# Raspi-TPUART.net
KiCad netlist of a schematic drawn in EAGLE
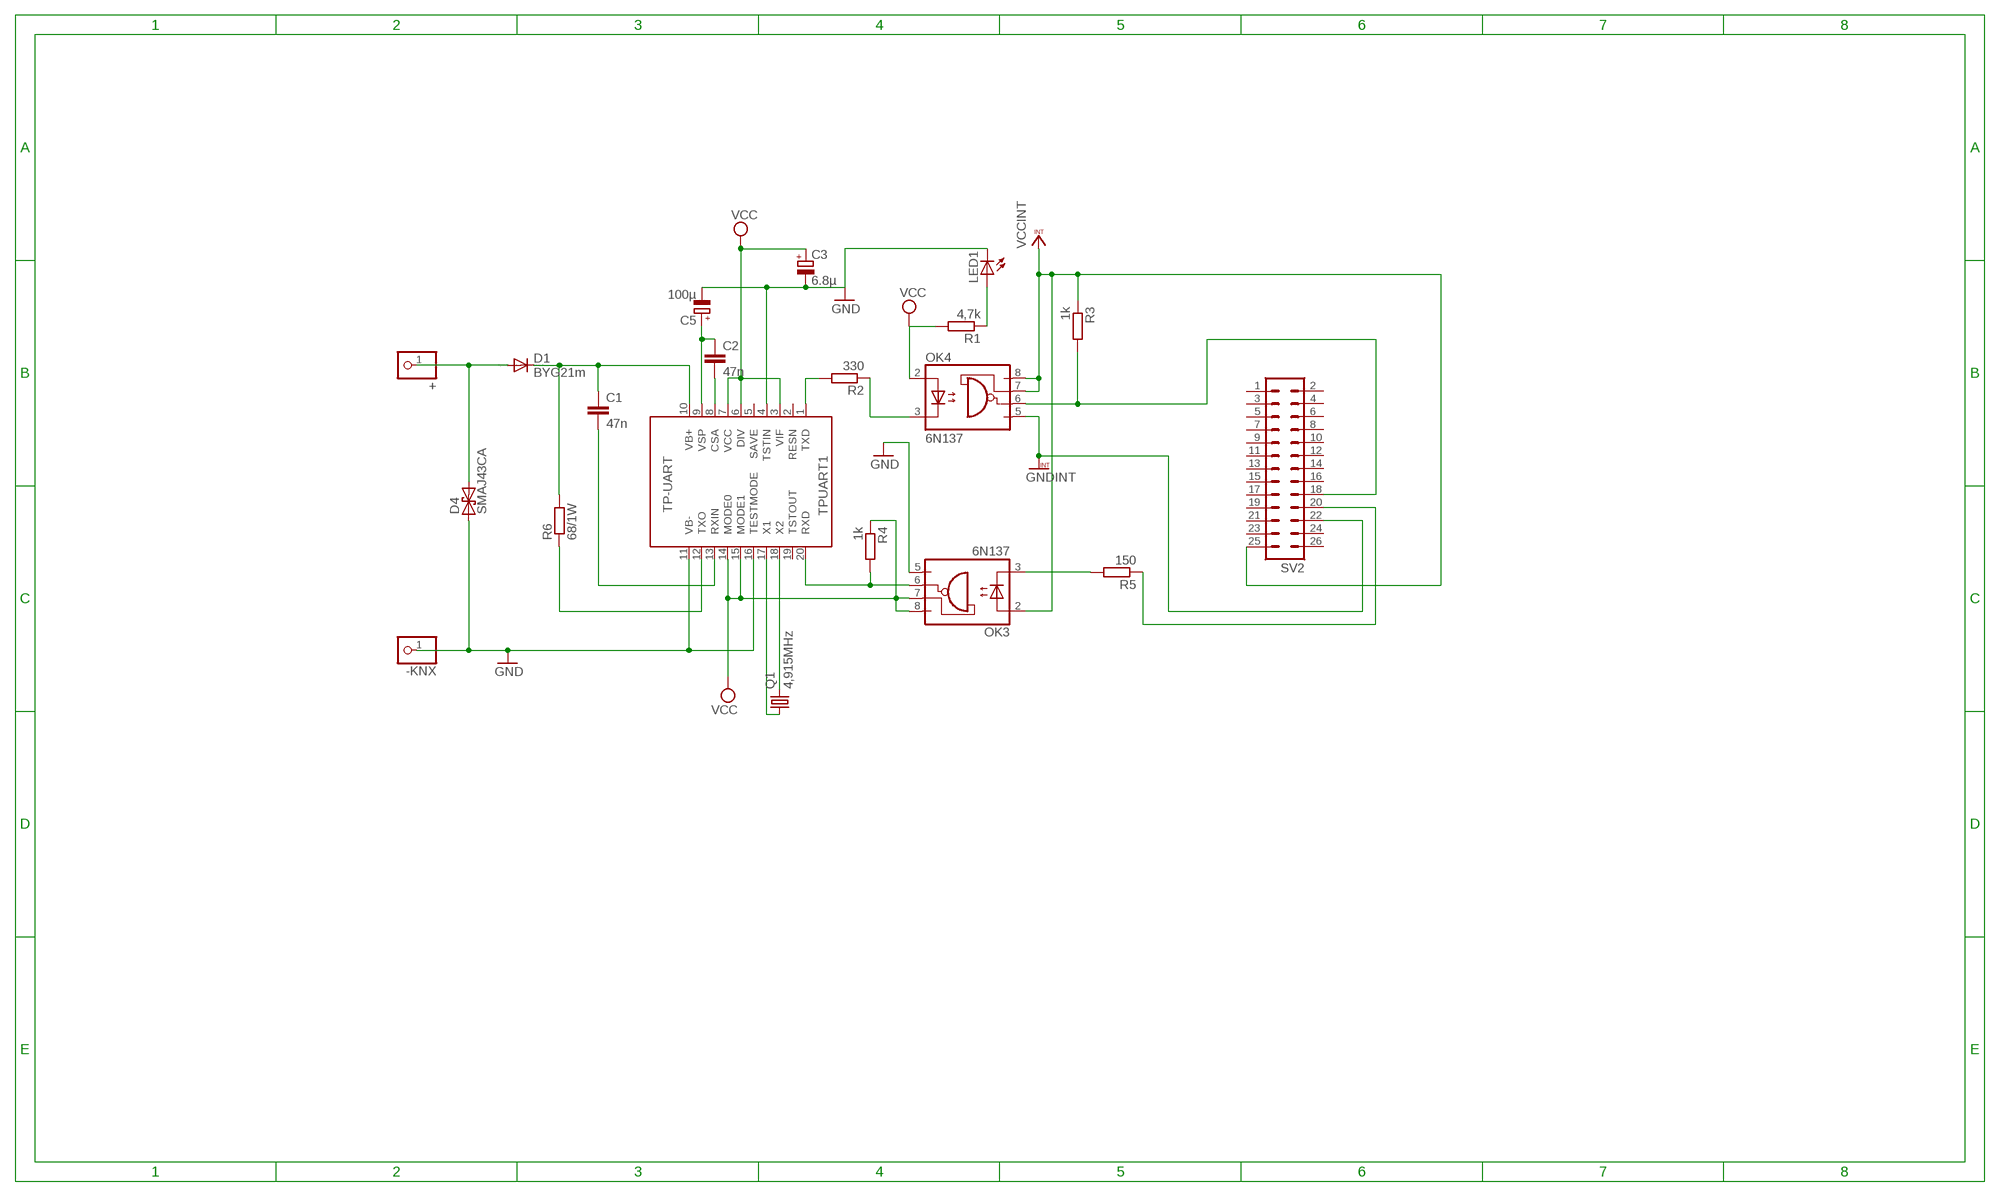
[diagram p0: schematic, sheet 1]

(export (version "E")
  (design (tool "Eeschema 10.0.6"))
  (components
    (comp (ref "+")
      (value "PINHD-1X1")
      (footprint "eagle-import:1X01")
      (libsource (lib "eagle-import") (part "PINHD-1X1"))
    )
    (comp (ref "-KNX")
      (value "PINHD-1X1")
      (footprint "eagle-import:1X01")
      (libsource (lib "eagle-import") (part "PINHD-1X1"))
    )
    (comp (ref "C1")
      (value "47n")
      (footprint "eagle-import:C1206")
      (libsource (lib "eagle-import") (part "C-EUC1206"))
    )
    (comp (ref "C2")
      (value "47n")
      (footprint "eagle-import:C1206")
      (libsource (lib "eagle-import") (part "C-EUC1206"))
    )
    (comp (ref "C3")
      (value "6.8µ")
      (footprint "eagle-import:CT7343")
      (libsource (lib "eagle-import") (part "CPOL-EUCT7343"))
    )
    (comp (ref "C5")
      (value "100µ")
      (footprint "eagle-import:CT7343")
      (libsource (lib "eagle-import") (part "CPOL-EUCT7343"))
    )
    (comp (ref "D1")
      (value "BYG21m")
      (footprint "eagle-import:SMB")
      (libsource (lib "eagle-import") (part "ES2D"))
    )
    (comp (ref "D4")
      (value "SMAJ43CA")
      (footprint "eagle-import:DO214AA")
      (libsource (lib "eagle-import") (part "BZW04XXB"))
    )
    (comp (ref "LED1")
      (value "LEDKA-3528ASYC")
      (footprint "eagle-import:KA-3528ASYC")
      (libsource (lib "eagle-import") (part "LEDKA-3528ASYC"))
    )
    (comp (ref "OK3")
      (value "6N137")
      (footprint "eagle-import:DIL8-SMD")
      (libsource (lib "eagle-import") (part "6N137"))
    )
    (comp (ref "OK4")
      (value "6N137")
      (footprint "eagle-import:DIL8-SMD")
      (libsource (lib "eagle-import") (part "6N137"))
    )
    (comp (ref "Q1")
      (value "4,915MHz")
      (footprint "eagle-import:HC49UP")
      (libsource (lib "eagle-import") (part "CRYSTALHC49UP"))
    )
    (comp (ref "R1")
      (value "4,7k")
      (footprint "eagle-import:M1206")
      (libsource (lib "eagle-import") (part "R-EU_M1206"))
    )
    (comp (ref "R2")
      (value "330")
      (footprint "eagle-import:M1206")
      (libsource (lib "eagle-import") (part "R-EU_M1206"))
    )
    (comp (ref "R3")
      (value "1k")
      (footprint "eagle-import:M1206")
      (libsource (lib "eagle-import") (part "R-EU_M1206"))
    )
    (comp (ref "R4")
      (value "1k")
      (footprint "eagle-import:M1206")
      (libsource (lib "eagle-import") (part "R-EU_M1206"))
    )
    (comp (ref "R5")
      (value "150")
      (footprint "eagle-import:M1206")
      (libsource (lib "eagle-import") (part "R-EU_M1206"))
    )
    (comp (ref "R6")
      (value "68/1W")
      (footprint "eagle-import:R2512")
      (libsource (lib "eagle-import") (part "R-EU_R2512"))
    )
    (comp (ref "SV2")
      (value "MA13-2")
      (footprint "eagle-import:MA13-2")
      (libsource (lib "eagle-import") (part "MA13-2"))
    )
    (comp (ref "TPUART1")
      (value "TP-UART")
      (footprint "eagle-import:SOIC20")
      (libsource (lib "eagle-import") (part "TP-UART"))
    )
  )
  (nets
    (net (code "1") (name "GND") (class "Default")
      (node (ref "-KNX") (pin "1") (pinfunction "1_1") (pintype "passive"))
      (node (ref "C3") (pin "-") (pinfunction "-_-") (pintype "passive"))
      (node (ref "C5") (pin "-") (pinfunction "-_-") (pintype "passive"))
      (node (ref "D4") (pin "A") (pinfunction "1_A") (pintype "passive"))
      (node (ref "LED1") (pin "C") (pinfunction "C_C") (pintype "passive"))
      (node (ref "OK3") (pin "5") (pinfunction "GND_5") (pintype "passive"))
      (node (ref "TPUART1") (pin "11") (pinfunction "VB-_11") (pintype "passive"))
      (node (ref "TPUART1") (pin "16") (pinfunction "TESTMODE_16") (pintype "input"))
      (node (ref "TPUART1") (pin "4") (pinfunction "TSTIN_4") (pintype "bidirectional"))
    )
    (net (code "2") (name "GNDINT") (class "Default")
      (node (ref "OK4") (pin "5") (pinfunction "GND_5") (pintype "passive"))
      (node (ref "SV2") (pin "22") (pinfunction "22_22") (pintype "passive"))
    )
    (net (code "3") (name "Net-(D4-2)") (class "Default")
      (node (ref "+") (pin "1") (pinfunction "1_1") (pintype "passive"))
      (node (ref "D1") (pin "A") (pinfunction "A_A") (pintype "passive"))
      (node (ref "D4") (pin "C") (pinfunction "2_C") (pintype "passive"))
    )
    (net (code "4") (name "Net-(LED1-PadA)") (class "Default")
      (node (ref "LED1") (pin "A") (pinfunction "A_A") (pintype "passive"))
      (node (ref "R1") (pin "1") (pinfunction "1_1") (pintype "passive"))
    )
    (net (code "5") (name "Net-(OK3-C)") (class "Default")
      (node (ref "OK3") (pin "3") (pinfunction "C_3") (pintype "passive"))
      (node (ref "R5") (pin "2") (pinfunction "2_2") (pintype "passive"))
    )
    (net (code "6") (name "Net-(OK3-VO)") (class "Default")
      (node (ref "OK3") (pin "6") (pinfunction "VO_6") (pintype "passive"))
      (node (ref "R4") (pin "2") (pinfunction "2_2") (pintype "passive"))
      (node (ref "TPUART1") (pin "20") (pinfunction "RXD_20") (pintype "input"))
    )
    (net (code "7") (name "Net-(OK4-C)") (class "Default")
      (node (ref "OK4") (pin "3") (pinfunction "C_3") (pintype "passive"))
      (node (ref "R2") (pin "1") (pinfunction "1_1") (pintype "passive"))
    )
    (net (code "8") (name "Net-(OK4-VO)") (class "Default")
      (node (ref "OK4") (pin "6") (pinfunction "VO_6") (pintype "passive"))
      (node (ref "R3") (pin "2") (pinfunction "2_2") (pintype "passive"))
      (node (ref "SV2") (pin "18") (pinfunction "18_18") (pintype "passive"))
    )
    (net (code "9") (name "Net-(R5-Pad1)") (class "Default")
      (node (ref "R5") (pin "1") (pinfunction "1_1") (pintype "passive"))
      (node (ref "SV2") (pin "20") (pinfunction "20_20") (pintype "passive"))
    )
    (net (code "10") (name "Net-(TPUART1-CSA)") (class "Default")
      (node (ref "C2") (pin "2") (pinfunction "2_2") (pintype "passive"))
      (node (ref "TPUART1") (pin "8") (pinfunction "CSA_8") (pintype "passive"))
    )
    (net (code "11") (name "Net-(TPUART1-RXIN)") (class "Default")
      (node (ref "C1") (pin "2") (pinfunction "2_2") (pintype "passive"))
      (node (ref "TPUART1") (pin "13") (pinfunction "RXIN_13") (pintype "input"))
    )
    (net (code "12") (name "Net-(TPUART1-TXD)") (class "Default")
      (node (ref "R2") (pin "2") (pinfunction "2_2") (pintype "passive"))
      (node (ref "TPUART1") (pin "1") (pinfunction "TXD_1") (pintype "output"))
    )
    (net (code "13") (name "Net-(TPUART1-TXO)") (class "Default")
      (node (ref "R6") (pin "1") (pinfunction "1_1") (pintype "passive"))
      (node (ref "TPUART1") (pin "12") (pinfunction "TXO_12") (pintype "output"))
    )
    (net (code "14") (name "Net-(TPUART1-VB+)") (class "Default")
      (node (ref "C1") (pin "1") (pinfunction "1_1") (pintype "passive"))
      (node (ref "D1") (pin "C") (pinfunction "C_C") (pintype "passive"))
      (node (ref "R6") (pin "2") (pinfunction "2_2") (pintype "passive"))
      (node (ref "TPUART1") (pin "10") (pinfunction "VB+_10") (pintype "passive"))
    )
    (net (code "15") (name "Net-(TPUART1-VSP)") (class "Default")
      (node (ref "C2") (pin "1") (pinfunction "1_1") (pintype "passive"))
      (node (ref "C5") (pin "+") (pinfunction "+_+") (pintype "passive"))
      (node (ref "TPUART1") (pin "9") (pinfunction "VSP_9") (pintype "passive"))
    )
    (net (code "16") (name "Net-(TPUART1-X1)") (class "Default")
      (node (ref "Q1") (pin "1") (pinfunction "1_1") (pintype "passive"))
      (node (ref "TPUART1") (pin "17") (pinfunction "X1_17") (pintype "passive"))
    )
    (net (code "17") (name "Net-(TPUART1-X2)") (class "Default")
      (node (ref "Q1") (pin "2") (pinfunction "2_2") (pintype "passive"))
      (node (ref "TPUART1") (pin "18") (pinfunction "X2_18") (pintype "passive"))
    )
    (net (code "18") (name "VCC") (class "Default")
      (node (ref "C3") (pin "+") (pinfunction "+_+") (pintype "passive"))
      (node (ref "OK3") (pin "7") (pinfunction "VE_7") (pintype "passive"))
      (node (ref "OK3") (pin "8") (pinfunction "VCC_8") (pintype "passive"))
      (node (ref "OK4") (pin "2") (pinfunction "A_2") (pintype "passive"))
      (node (ref "R1") (pin "2") (pinfunction "2_2") (pintype "passive"))
      (node (ref "R4") (pin "1") (pinfunction "1_1") (pintype "passive"))
      (node (ref "TPUART1") (pin "14") (pinfunction "MODE0_14") (pintype "input"))
      (node (ref "TPUART1") (pin "15") (pinfunction "MODE1_15") (pintype "input"))
      (node (ref "TPUART1") (pin "3") (pinfunction "VIF_3") (pintype "input"))
      (node (ref "TPUART1") (pin "6") (pinfunction "DIV_6") (pintype "input"))
      (node (ref "TPUART1") (pin "7") (pinfunction "VCC_7") (pintype "output"))
    )
    (net (code "19") (name "VCCINT") (class "Default")
      (node (ref "OK3") (pin "2") (pinfunction "A_2") (pintype "passive"))
      (node (ref "OK4") (pin "7") (pinfunction "VE_7") (pintype "passive"))
      (node (ref "OK4") (pin "8") (pinfunction "VCC_8") (pintype "passive"))
      (node (ref "R3") (pin "1") (pinfunction "1_1") (pintype "passive"))
      (node (ref "SV2") (pin "25") (pinfunction "25_25") (pintype "passive"))
    )
    (net (code "20") (name "unconnected-(SV2-Pad1)") (class "Default")
      (node (ref "SV2") (pin "1") (pinfunction "1_1") (pintype "passive"))
    )
    (net (code "21") (name "unconnected-(SV2-Pad2)") (class "Default")
      (node (ref "SV2") (pin "2") (pinfunction "2_2") (pintype "passive"))
    )
    (net (code "22") (name "unconnected-(SV2-Pad3)") (class "Default")
      (node (ref "SV2") (pin "3") (pinfunction "3_3") (pintype "passive"))
    )
    (net (code "23") (name "unconnected-(SV2-Pad4)") (class "Default")
      (node (ref "SV2") (pin "4") (pinfunction "4_4") (pintype "passive"))
    )
    (net (code "24") (name "unconnected-(SV2-Pad5)") (class "Default")
      (node (ref "SV2") (pin "5") (pinfunction "5_5") (pintype "passive"))
    )
    (net (code "25") (name "unconnected-(SV2-Pad6)") (class "Default")
      (node (ref "SV2") (pin "6") (pinfunction "6_6") (pintype "passive"))
    )
    (net (code "26") (name "unconnected-(SV2-Pad7)") (class "Default")
      (node (ref "SV2") (pin "7") (pinfunction "7_7") (pintype "passive"))
    )
    (net (code "27") (name "unconnected-(SV2-Pad8)") (class "Default")
      (node (ref "SV2") (pin "8") (pinfunction "8_8") (pintype "passive"))
    )
    (net (code "28") (name "unconnected-(SV2-Pad9)") (class "Default")
      (node (ref "SV2") (pin "9") (pinfunction "9_9") (pintype "passive"))
    )
    (net (code "29") (name "unconnected-(SV2-Pad10)") (class "Default")
      (node (ref "SV2") (pin "10") (pinfunction "10_10") (pintype "passive"))
    )
    (net (code "30") (name "unconnected-(SV2-Pad11)") (class "Default")
      (node (ref "SV2") (pin "11") (pinfunction "11_11") (pintype "passive"))
    )
    (net (code "31") (name "unconnected-(SV2-Pad12)") (class "Default")
      (node (ref "SV2") (pin "12") (pinfunction "12_12") (pintype "passive"))
    )
    (net (code "32") (name "unconnected-(SV2-Pad13)") (class "Default")
      (node (ref "SV2") (pin "13") (pinfunction "13_13") (pintype "passive"))
    )
    (net (code "33") (name "unconnected-(SV2-Pad14)") (class "Default")
      (node (ref "SV2") (pin "14") (pinfunction "14_14") (pintype "passive"))
    )
    (net (code "34") (name "unconnected-(SV2-Pad15)") (class "Default")
      (node (ref "SV2") (pin "15") (pinfunction "15_15") (pintype "passive"))
    )
    (net (code "35") (name "unconnected-(SV2-Pad16)") (class "Default")
      (node (ref "SV2") (pin "16") (pinfunction "16_16") (pintype "passive"))
    )
    (net (code "36") (name "unconnected-(SV2-Pad17)") (class "Default")
      (node (ref "SV2") (pin "17") (pinfunction "17_17") (pintype "passive"))
    )
    (net (code "37") (name "unconnected-(SV2-Pad19)") (class "Default")
      (node (ref "SV2") (pin "19") (pinfunction "19_19") (pintype "passive"))
    )
    (net (code "38") (name "unconnected-(SV2-Pad21)") (class "Default")
      (node (ref "SV2") (pin "21") (pinfunction "21_21") (pintype "passive"))
    )
    (net (code "39") (name "unconnected-(SV2-Pad23)") (class "Default")
      (node (ref "SV2") (pin "23") (pinfunction "23_23") (pintype "passive"))
    )
    (net (code "40") (name "unconnected-(SV2-Pad24)") (class "Default")
      (node (ref "SV2") (pin "24") (pinfunction "24_24") (pintype "passive"))
    )
    (net (code "41") (name "unconnected-(SV2-Pad26)") (class "Default")
      (node (ref "SV2") (pin "26") (pinfunction "26_26") (pintype "passive"))
    )
    (net (code "42") (name "unconnected-(TPUART1-RESN-Pad2)") (class "Default")
      (node (ref "TPUART1") (pin "2") (pinfunction "RESN_2") (pintype "bidirectional"))
    )
    (net (code "43") (name "unconnected-(TPUART1-SAVE-Pad5)") (class "Default")
      (node (ref "TPUART1") (pin "5") (pinfunction "SAVE_5") (pintype "open_collector"))
    )
    (net (code "44") (name "unconnected-(TPUART1-TSTOUT-Pad19)") (class "Default")
      (node (ref "TPUART1") (pin "19") (pinfunction "TSTOUT_19") (pintype "output"))
    )
  )
)
